# basicDueMega.net
KiCad netlist of a schematic drawn in EAGLE
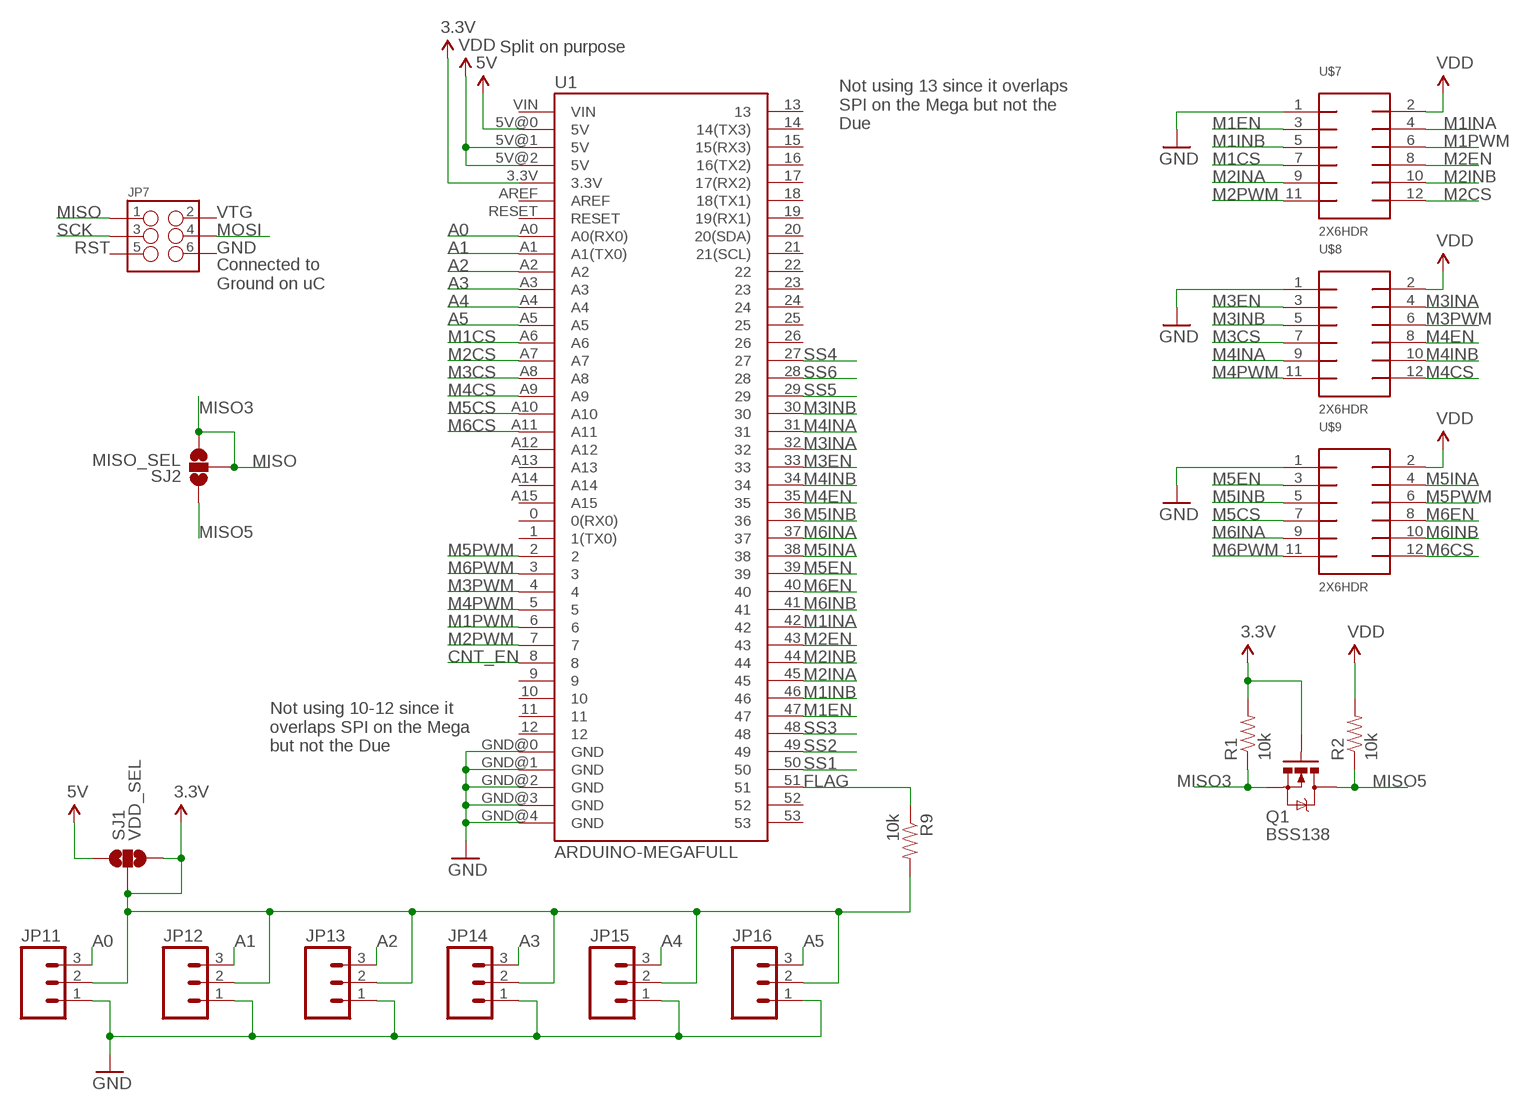
[diagram p0: schematic, sheet 1]
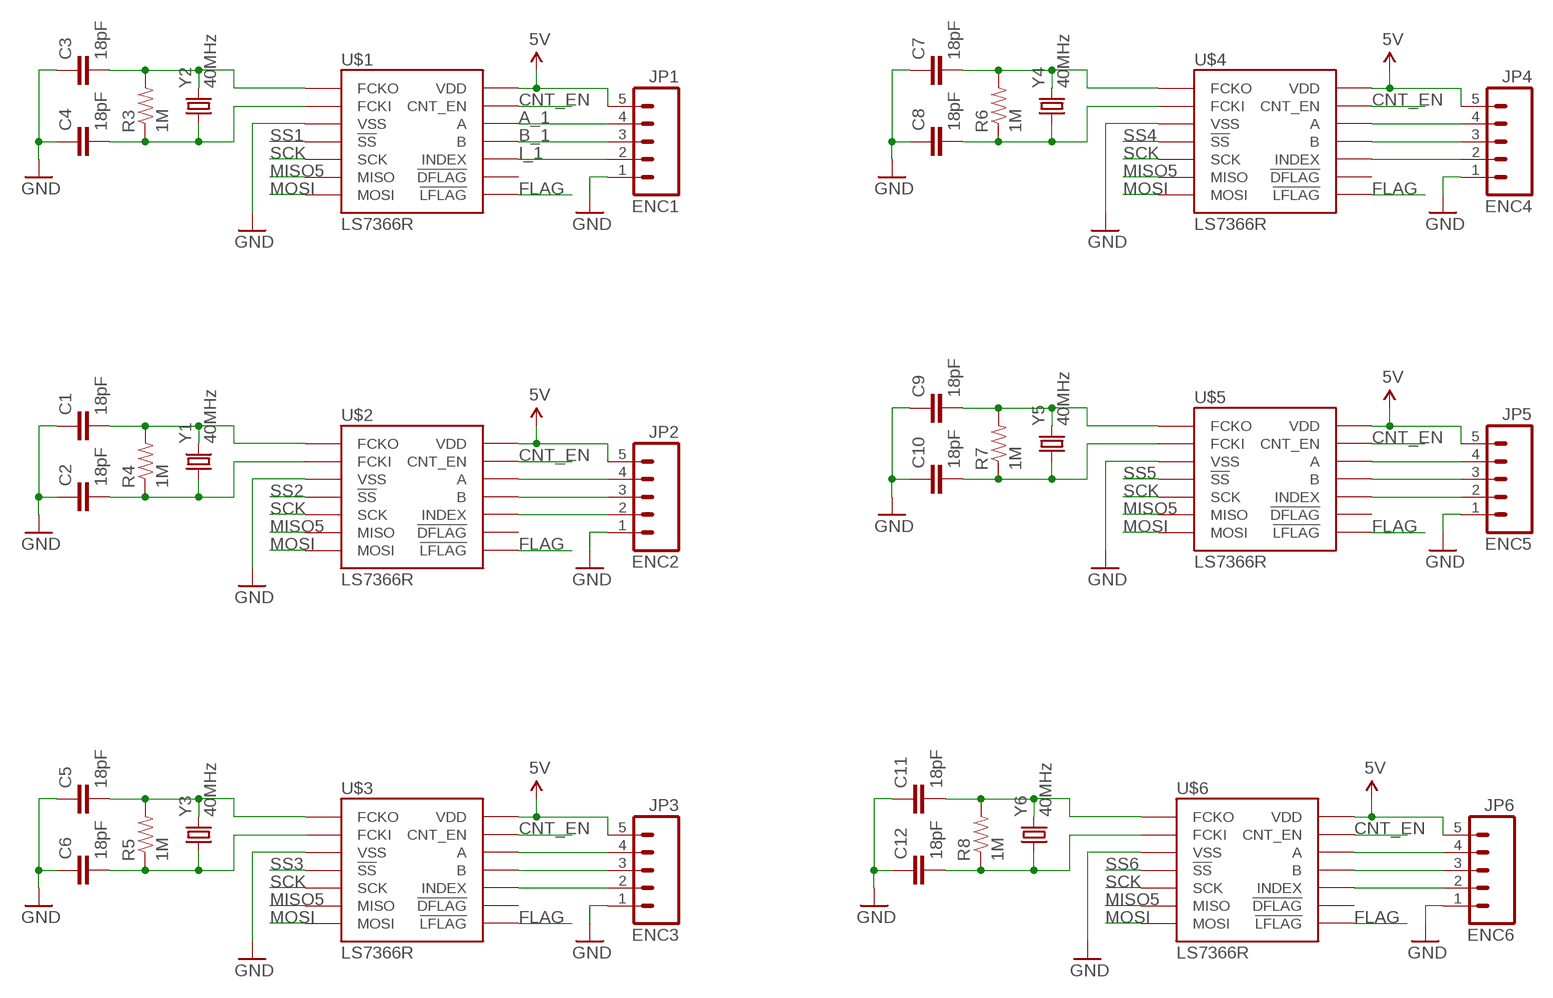
[diagram p1: schematic, sheet 2]

(export (version "E")
  (design (tool "Eeschema 10.0.6"))
  (components
    (comp (ref "C1")
      (value "18pF")
      (footprint "eagle-import:0603-CAP")
      (libsource (lib "eagle-import") (part "CAP0603-CAP"))
    )
    (comp (ref "C2")
      (value "18pF")
      (footprint "eagle-import:0603-CAP")
      (libsource (lib "eagle-import") (part "CAP0603-CAP"))
    )
    (comp (ref "C3")
      (value "18pF")
      (footprint "eagle-import:0603-CAP")
      (libsource (lib "eagle-import") (part "CAP0603-CAP"))
    )
    (comp (ref "C4")
      (value "18pF")
      (footprint "eagle-import:0603-CAP")
      (libsource (lib "eagle-import") (part "CAP0603-CAP"))
    )
    (comp (ref "C5")
      (value "18pF")
      (footprint "eagle-import:0603-CAP")
      (libsource (lib "eagle-import") (part "CAP0603-CAP"))
    )
    (comp (ref "C6")
      (value "18pF")
      (footprint "eagle-import:0603-CAP")
      (libsource (lib "eagle-import") (part "CAP0603-CAP"))
    )
    (comp (ref "C7")
      (value "18pF")
      (footprint "eagle-import:0603-CAP")
      (libsource (lib "eagle-import") (part "CAP0603-CAP"))
    )
    (comp (ref "C8")
      (value "18pF")
      (footprint "eagle-import:0603-CAP")
      (libsource (lib "eagle-import") (part "CAP0603-CAP"))
    )
    (comp (ref "C9")
      (value "18pF")
      (footprint "eagle-import:0603-CAP")
      (libsource (lib "eagle-import") (part "CAP0603-CAP"))
    )
    (comp (ref "C10")
      (value "18pF")
      (footprint "eagle-import:0603-CAP")
      (libsource (lib "eagle-import") (part "CAP0603-CAP"))
    )
    (comp (ref "C11")
      (value "18pF")
      (footprint "eagle-import:0603-CAP")
      (libsource (lib "eagle-import") (part "CAP0603-CAP"))
    )
    (comp (ref "C12")
      (value "18pF")
      (footprint "eagle-import:0603-CAP")
      (libsource (lib "eagle-import") (part "CAP0603-CAP"))
    )
    (comp (ref "JP1")
      (value "ENC1")
      (footprint "eagle-import:1X05_LOCK")
      (libsource (lib "eagle-import") (part "M05LOCK"))
    )
    (comp (ref "JP2")
      (value "ENC2")
      (footprint "eagle-import:1X05_LOCK")
      (libsource (lib "eagle-import") (part "M05LOCK"))
    )
    (comp (ref "JP3")
      (value "ENC3")
      (footprint "eagle-import:1X05_LOCK")
      (libsource (lib "eagle-import") (part "M05LOCK"))
    )
    (comp (ref "JP4")
      (value "ENC4")
      (footprint "eagle-import:1X05_LOCK")
      (libsource (lib "eagle-import") (part "M05LOCK"))
    )
    (comp (ref "JP5")
      (value "ENC5")
      (footprint "eagle-import:1X05_LOCK")
      (libsource (lib "eagle-import") (part "M05LOCK"))
    )
    (comp (ref "JP6")
      (value "ENC6")
      (footprint "eagle-import:1X05_LOCK")
      (libsource (lib "eagle-import") (part "M05LOCK"))
    )
    (comp (ref "R3")
      (value "1M")
      (footprint "eagle-import:0603-RES")
      (libsource (lib "eagle-import") (part "RESISTOR0603-RES"))
    )
    (comp (ref "R4")
      (value "1M")
      (footprint "eagle-import:0603-RES")
      (libsource (lib "eagle-import") (part "RESISTOR0603-RES"))
    )
    (comp (ref "R5")
      (value "1M")
      (footprint "eagle-import:0603-RES")
      (libsource (lib "eagle-import") (part "RESISTOR0603-RES"))
    )
    (comp (ref "R6")
      (value "1M")
      (footprint "eagle-import:0603-RES")
      (libsource (lib "eagle-import") (part "RESISTOR0603-RES"))
    )
    (comp (ref "R7")
      (value "1M")
      (footprint "eagle-import:0603-RES")
      (libsource (lib "eagle-import") (part "RESISTOR0603-RES"))
    )
    (comp (ref "R8")
      (value "1M")
      (footprint "eagle-import:0603-RES")
      (libsource (lib "eagle-import") (part "RESISTOR0603-RES"))
    )
    (comp (ref "U$1")
      (value "LS7366R")
      (footprint "eagle-import:SOIC14")
      (libsource (lib "eagle-import") (part "LS7366R"))
    )
    (comp (ref "U$2")
      (value "LS7366R")
      (footprint "eagle-import:SOIC14")
      (libsource (lib "eagle-import") (part "LS7366R"))
    )
    (comp (ref "U$3")
      (value "LS7366R")
      (footprint "eagle-import:SOIC14")
      (libsource (lib "eagle-import") (part "LS7366R"))
    )
    (comp (ref "U$4")
      (value "LS7366R")
      (footprint "eagle-import:SOIC14")
      (libsource (lib "eagle-import") (part "LS7366R"))
    )
    (comp (ref "U$5")
      (value "LS7366R")
      (footprint "eagle-import:SOIC14")
      (libsource (lib "eagle-import") (part "LS7366R"))
    )
    (comp (ref "U$6")
      (value "LS7366R")
      (footprint "eagle-import:SOIC14")
      (libsource (lib "eagle-import") (part "LS7366R"))
    )
    (comp (ref "Y1")
      (value "40MHz")
      (footprint "eagle-import:CRYSTAL-SMD-5X3")
      (libsource (lib "eagle-import") (part "CRYSTAL5X3"))
    )
    (comp (ref "Y2")
      (value "40MHz")
      (footprint "eagle-import:CRYSTAL-SMD-5X3")
      (libsource (lib "eagle-import") (part "CRYSTAL5X3"))
    )
    (comp (ref "Y3")
      (value "40MHz")
      (footprint "eagle-import:CRYSTAL-SMD-5X3")
      (libsource (lib "eagle-import") (part "CRYSTAL5X3"))
    )
    (comp (ref "Y4")
      (value "40MHz")
      (footprint "eagle-import:CRYSTAL-SMD-5X3")
      (libsource (lib "eagle-import") (part "CRYSTAL5X3"))
    )
    (comp (ref "Y5")
      (value "40MHz")
      (footprint "eagle-import:CRYSTAL-SMD-5X3")
      (libsource (lib "eagle-import") (part "CRYSTAL5X3"))
    )
    (comp (ref "Y6")
      (value "40MHz")
      (footprint "eagle-import:CRYSTAL-SMD-5X3")
      (libsource (lib "eagle-import") (part "CRYSTAL5X3"))
    )
    (comp (ref "JP7")
      (value "M03X2POGO_PINS")
      (footprint "eagle-import:2X3_POGO")
      (libsource (lib "eagle-import") (part "M03X2POGO_PINS"))
    )
    (comp (ref "JP11")
      (value "M03LOCK")
      (footprint "eagle-import:1X03_LOCK")
      (libsource (lib "eagle-import") (part "M03LOCK"))
    )
    (comp (ref "JP12")
      (value "M03LOCK")
      (footprint "eagle-import:1X03_LOCK")
      (libsource (lib "eagle-import") (part "M03LOCK"))
    )
    (comp (ref "JP13")
      (value "M03LOCK")
      (footprint "eagle-import:1X03_LOCK")
      (libsource (lib "eagle-import") (part "M03LOCK"))
    )
    (comp (ref "JP14")
      (value "M03LOCK")
      (footprint "eagle-import:1X03_LOCK")
      (libsource (lib "eagle-import") (part "M03LOCK"))
    )
    (comp (ref "JP15")
      (value "M03LOCK")
      (footprint "eagle-import:1X03_LOCK")
      (libsource (lib "eagle-import") (part "M03LOCK"))
    )
    (comp (ref "JP16")
      (value "M03LOCK")
      (footprint "eagle-import:1X03_LOCK")
      (libsource (lib "eagle-import") (part "M03LOCK"))
    )
    (comp (ref "Q1")
      (value "MOSFET-NCHANNELBSS123LT1G")
      (footprint "eagle-import:SOT23")
      (libsource (lib "eagle-import") (part "MOSFET-NCHANNELBSS123LT1G"))
    )
    (comp (ref "R1")
      (value "10k")
      (footprint "eagle-import:0603-RES")
      (libsource (lib "eagle-import") (part "RESISTOR0603-RES"))
    )
    (comp (ref "R2")
      (value "10k")
      (footprint "eagle-import:0603-RES")
      (libsource (lib "eagle-import") (part "RESISTOR0603-RES"))
    )
    (comp (ref "R9")
      (value "10k")
      (footprint "eagle-import:0603-RES")
      (libsource (lib "eagle-import") (part "RESISTOR0603-RES"))
    )
    (comp (ref "SJ1")
      (value "VDD_SEL")
      (footprint "eagle-import:SJ_2")
      (libsource (lib "eagle-import") (part "SOLDERJUMPER_2WAYT"))
    )
    (comp (ref "SJ2")
      (value "MISO_SEL")
      (footprint "eagle-import:SJ_2")
      (libsource (lib "eagle-import") (part "SOLDERJUMPER_2WAYT"))
    )
    (comp (ref "U$7")
      (value "2X6HDR")
      (footprint "eagle-import:2X6_2MM_SHROUD")
      (libsource (lib "eagle-import") (part "2X6HDR"))
    )
    (comp (ref "U$8")
      (value "2X6HDR")
      (footprint "eagle-import:2X6_2MM_SHROUD")
      (libsource (lib "eagle-import") (part "2X6HDR"))
    )
    (comp (ref "U$9")
      (value "2X6HDR")
      (footprint "eagle-import:2X6_2MM_SHROUD")
      (libsource (lib "eagle-import") (part "2X6HDR"))
    )
    (comp (ref "U1")
      (value "ARDUINO-MEGAFULL")
      (footprint "eagle-import:ARDUINO_MEGA")
      (libsource (lib "eagle-import") (part "ARDUINO-MEGAFULL"))
    )
  )
  (nets
    (net (code "1") (name "3.3V") (class "Default")
      (node (ref "JP11") (pin "2") (pinfunction "2_2") (pintype "passive"))
      (node (ref "JP12") (pin "2") (pinfunction "2_2") (pintype "passive"))
      (node (ref "JP13") (pin "2") (pinfunction "2_2") (pintype "passive"))
      (node (ref "JP14") (pin "2") (pinfunction "2_2") (pintype "passive"))
      (node (ref "JP15") (pin "2") (pinfunction "2_2") (pintype "passive"))
      (node (ref "JP16") (pin "2") (pinfunction "2_2") (pintype "passive"))
      (node (ref "Q1") (pin "1") (pinfunction "G_1") (pintype "passive"))
      (node (ref "R1") (pin "2") (pinfunction "2_2") (pintype "passive"))
      (node (ref "R9") (pin "2") (pinfunction "2_2") (pintype "passive"))
      (node (ref "SJ1") (pin "2") (pinfunction "2_2") (pintype "passive"))
      (node (ref "SJ1") (pin "3") (pinfunction "3_3") (pintype "passive"))
      (node (ref "U1") (pin "3.3V") (pinfunction "3.3V_3.3V") (pintype "bidirectional"))
    )
    (net (code "2") (name "5V") (class "Default")
      (node (ref "JP1") (pin "5") (pinfunction "5_5") (pintype "passive"))
      (node (ref "JP2") (pin "5") (pinfunction "5_5") (pintype "passive"))
      (node (ref "JP3") (pin "5") (pinfunction "5_5") (pintype "passive"))
      (node (ref "JP4") (pin "5") (pinfunction "5_5") (pintype "passive"))
      (node (ref "JP5") (pin "5") (pinfunction "5_5") (pintype "passive"))
      (node (ref "JP6") (pin "5") (pinfunction "5_5") (pintype "passive"))
      (node (ref "SJ1") (pin "1") (pinfunction "1_1") (pintype "passive"))
      (node (ref "U$1") (pin "14") (pinfunction "VDD_14") (pintype "bidirectional"))
      (node (ref "U$2") (pin "14") (pinfunction "VDD_14") (pintype "bidirectional"))
      (node (ref "U$3") (pin "14") (pinfunction "VDD_14") (pintype "bidirectional"))
      (node (ref "U$4") (pin "14") (pinfunction "VDD_14") (pintype "bidirectional"))
      (node (ref "U$5") (pin "14") (pinfunction "VDD_14") (pintype "bidirectional"))
      (node (ref "U$6") (pin "14") (pinfunction "VDD_14") (pintype "bidirectional"))
      (node (ref "U1") (pin "5V@0") (pinfunction "5V_5V@0") (pintype "bidirectional"))
    )
    (net (code "3") (name "A0") (class "Default")
      (node (ref "JP11") (pin "3") (pinfunction "3_3") (pintype "passive"))
      (node (ref "U1") (pin "A0") (pinfunction "A0(RX0)_A0") (pintype "bidirectional"))
    )
    (net (code "4") (name "A1") (class "Default")
      (node (ref "JP12") (pin "3") (pinfunction "3_3") (pintype "passive"))
      (node (ref "U1") (pin "A1") (pinfunction "A1(TX0)_A1") (pintype "bidirectional"))
    )
    (net (code "5") (name "A2") (class "Default")
      (node (ref "JP13") (pin "3") (pinfunction "3_3") (pintype "passive"))
      (node (ref "U1") (pin "A2") (pinfunction "A2_A2") (pintype "bidirectional"))
    )
    (net (code "6") (name "A3") (class "Default")
      (node (ref "JP14") (pin "3") (pinfunction "3_3") (pintype "passive"))
      (node (ref "U1") (pin "A3") (pinfunction "A3_A3") (pintype "bidirectional"))
    )
    (net (code "7") (name "A4") (class "Default")
      (node (ref "JP15") (pin "3") (pinfunction "3_3") (pintype "passive"))
      (node (ref "U1") (pin "A4") (pinfunction "A4_A4") (pintype "bidirectional"))
    )
    (net (code "8") (name "A5") (class "Default")
      (node (ref "JP16") (pin "3") (pinfunction "3_3") (pintype "passive"))
      (node (ref "U1") (pin "A5") (pinfunction "A5_A5") (pintype "bidirectional"))
    )
    (net (code "9") (name "A_1") (class "Default")
      (node (ref "JP1") (pin "4") (pinfunction "4_4") (pintype "passive"))
      (node (ref "U$1") (pin "12") (pinfunction "A_12") (pintype "bidirectional"))
    )
    (net (code "10") (name "B_1") (class "Default")
      (node (ref "JP1") (pin "3") (pinfunction "3_3") (pintype "passive"))
      (node (ref "U$1") (pin "11") (pinfunction "B_11") (pintype "bidirectional"))
    )
    (net (code "11") (name "CNT_EN") (class "Default")
      (node (ref "U$1") (pin "13") (pinfunction "CNT_EN_13") (pintype "bidirectional"))
      (node (ref "U$2") (pin "13") (pinfunction "CNT_EN_13") (pintype "bidirectional"))
      (node (ref "U$3") (pin "13") (pinfunction "CNT_EN_13") (pintype "bidirectional"))
      (node (ref "U$4") (pin "13") (pinfunction "CNT_EN_13") (pintype "bidirectional"))
      (node (ref "U$5") (pin "13") (pinfunction "CNT_EN_13") (pintype "bidirectional"))
      (node (ref "U$6") (pin "13") (pinfunction "CNT_EN_13") (pintype "bidirectional"))
      (node (ref "U1") (pin "8") (pinfunction "8_8") (pintype "bidirectional"))
    )
    (net (code "12") (name "FLAG") (class "Default")
      (node (ref "R9") (pin "1") (pinfunction "1_1") (pintype "passive"))
      (node (ref "U$1") (pin "8") (pinfunction "~{LFLAG}_8") (pintype "bidirectional"))
      (node (ref "U$2") (pin "8") (pinfunction "~{LFLAG}_8") (pintype "bidirectional"))
      (node (ref "U$3") (pin "8") (pinfunction "~{LFLAG}_8") (pintype "bidirectional"))
      (node (ref "U$4") (pin "8") (pinfunction "~{LFLAG}_8") (pintype "bidirectional"))
      (node (ref "U$5") (pin "8") (pinfunction "~{LFLAG}_8") (pintype "bidirectional"))
      (node (ref "U$6") (pin "8") (pinfunction "~{LFLAG}_8") (pintype "bidirectional"))
      (node (ref "U1") (pin "51") (pinfunction "51_51") (pintype "bidirectional"))
    )
    (net (code "13") (name "GND") (class "Default")
      (node (ref "C1") (pin "1") (pinfunction "1_1") (pintype "passive"))
      (node (ref "C10") (pin "1") (pinfunction "1_1") (pintype "passive"))
      (node (ref "C11") (pin "1") (pinfunction "1_1") (pintype "passive"))
      (node (ref "C12") (pin "1") (pinfunction "1_1") (pintype "passive"))
      (node (ref "C2") (pin "1") (pinfunction "1_1") (pintype "passive"))
      (node (ref "C3") (pin "1") (pinfunction "1_1") (pintype "passive"))
      (node (ref "C4") (pin "1") (pinfunction "1_1") (pintype "passive"))
      (node (ref "C5") (pin "1") (pinfunction "1_1") (pintype "passive"))
      (node (ref "C6") (pin "1") (pinfunction "1_1") (pintype "passive"))
      (node (ref "C7") (pin "1") (pinfunction "1_1") (pintype "passive"))
      (node (ref "C8") (pin "1") (pinfunction "1_1") (pintype "passive"))
      (node (ref "C9") (pin "1") (pinfunction "1_1") (pintype "passive"))
      (node (ref "JP1") (pin "1") (pinfunction "1_1") (pintype "passive"))
      (node (ref "JP11") (pin "1") (pinfunction "1_1") (pintype "passive"))
      (node (ref "JP12") (pin "1") (pinfunction "1_1") (pintype "passive"))
      (node (ref "JP13") (pin "1") (pinfunction "1_1") (pintype "passive"))
      (node (ref "JP14") (pin "1") (pinfunction "1_1") (pintype "passive"))
      (node (ref "JP15") (pin "1") (pinfunction "1_1") (pintype "passive"))
      (node (ref "JP16") (pin "1") (pinfunction "1_1") (pintype "passive"))
      (node (ref "JP2") (pin "1") (pinfunction "1_1") (pintype "passive"))
      (node (ref "JP3") (pin "1") (pinfunction "1_1") (pintype "passive"))
      (node (ref "JP4") (pin "1") (pinfunction "1_1") (pintype "passive"))
      (node (ref "JP5") (pin "1") (pinfunction "1_1") (pintype "passive"))
      (node (ref "JP6") (pin "1") (pinfunction "1_1") (pintype "passive"))
      (node (ref "U$1") (pin "3") (pinfunction "VSS_3") (pintype "bidirectional"))
      (node (ref "U$2") (pin "3") (pinfunction "VSS_3") (pintype "bidirectional"))
      (node (ref "U$3") (pin "3") (pinfunction "VSS_3") (pintype "bidirectional"))
      (node (ref "U$4") (pin "3") (pinfunction "VSS_3") (pintype "bidirectional"))
      (node (ref "U$5") (pin "3") (pinfunction "VSS_3") (pintype "bidirectional"))
      (node (ref "U$6") (pin "3") (pinfunction "VSS_3") (pintype "bidirectional"))
      (node (ref "U$7") (pin "1") (pinfunction "P$1_1") (pintype "bidirectional"))
      (node (ref "U$8") (pin "1") (pinfunction "P$1_1") (pintype "bidirectional"))
      (node (ref "U$9") (pin "1") (pinfunction "P$1_1") (pintype "bidirectional"))
      (node (ref "U1") (pin "GND@0") (pinfunction "GND_GND@0") (pintype "bidirectional"))
      (node (ref "U1") (pin "GND@1") (pinfunction "GND_GND@1") (pintype "bidirectional"))
      (node (ref "U1") (pin "GND@2") (pinfunction "GND_GND@2") (pintype "bidirectional"))
      (node (ref "U1") (pin "GND@3") (pinfunction "GND_GND@3") (pintype "bidirectional"))
      (node (ref "U1") (pin "GND@4") (pinfunction "GND_GND@4") (pintype "bidirectional"))
    )
    (net (code "14") (name "I_1") (class "Default")
      (node (ref "JP1") (pin "2") (pinfunction "2_2") (pintype "passive"))
      (node (ref "U$1") (pin "10") (pinfunction "INDEX_10") (pintype "bidirectional"))
    )
    (net (code "15") (name "M1CS") (class "Default")
      (node (ref "U$7") (pin "7") (pinfunction "P$7_7") (pintype "bidirectional"))
      (node (ref "U1") (pin "A6") (pinfunction "A6_A6") (pintype "bidirectional"))
    )
    (net (code "16") (name "M1EN") (class "Default")
      (node (ref "U$7") (pin "3") (pinfunction "P$3_3") (pintype "bidirectional"))
      (node (ref "U1") (pin "47") (pinfunction "47_47") (pintype "bidirectional"))
    )
    (net (code "17") (name "M1INA") (class "Default")
      (node (ref "U$7") (pin "4") (pinfunction "P$4_4") (pintype "bidirectional"))
      (node (ref "U1") (pin "42") (pinfunction "42_42") (pintype "bidirectional"))
    )
    (net (code "18") (name "M1INB") (class "Default")
      (node (ref "U$7") (pin "5") (pinfunction "P$5_5") (pintype "bidirectional"))
      (node (ref "U1") (pin "46") (pinfunction "46_46") (pintype "bidirectional"))
    )
    (net (code "19") (name "M1PWM") (class "Default")
      (node (ref "U$7") (pin "6") (pinfunction "P$6_6") (pintype "bidirectional"))
      (node (ref "U1") (pin "6") (pinfunction "6_6") (pintype "bidirectional"))
    )
    (net (code "20") (name "M2CS") (class "Default")
      (node (ref "U$7") (pin "12") (pinfunction "P$12_12") (pintype "bidirectional"))
      (node (ref "U1") (pin "A7") (pinfunction "A7_A7") (pintype "bidirectional"))
    )
    (net (code "21") (name "M2EN") (class "Default")
      (node (ref "U$7") (pin "8") (pinfunction "P$8_8") (pintype "bidirectional"))
      (node (ref "U1") (pin "43") (pinfunction "43_43") (pintype "bidirectional"))
    )
    (net (code "22") (name "M2INA") (class "Default")
      (node (ref "U$7") (pin "9") (pinfunction "P$9_9") (pintype "bidirectional"))
      (node (ref "U1") (pin "45") (pinfunction "45_45") (pintype "bidirectional"))
    )
    (net (code "23") (name "M2INB") (class "Default")
      (node (ref "U$7") (pin "10") (pinfunction "P$10_10") (pintype "bidirectional"))
      (node (ref "U1") (pin "44") (pinfunction "44_44") (pintype "bidirectional"))
    )
    (net (code "24") (name "M2PWM") (class "Default")
      (node (ref "U$7") (pin "11") (pinfunction "P$11_11") (pintype "bidirectional"))
      (node (ref "U1") (pin "7") (pinfunction "7_7") (pintype "bidirectional"))
    )
    (net (code "25") (name "M3CS") (class "Default")
      (node (ref "U$8") (pin "7") (pinfunction "P$7_7") (pintype "bidirectional"))
      (node (ref "U1") (pin "A8") (pinfunction "A8_A8") (pintype "bidirectional"))
    )
    (net (code "26") (name "M3EN") (class "Default")
      (node (ref "U$8") (pin "3") (pinfunction "P$3_3") (pintype "bidirectional"))
      (node (ref "U1") (pin "33") (pinfunction "33_33") (pintype "bidirectional"))
    )
    (net (code "27") (name "M3INA") (class "Default")
      (node (ref "U$8") (pin "4") (pinfunction "P$4_4") (pintype "bidirectional"))
      (node (ref "U1") (pin "32") (pinfunction "32_32") (pintype "bidirectional"))
    )
    (net (code "28") (name "M3INB") (class "Default")
      (node (ref "U$8") (pin "5") (pinfunction "P$5_5") (pintype "bidirectional"))
      (node (ref "U1") (pin "30") (pinfunction "30_30") (pintype "bidirectional"))
    )
    (net (code "29") (name "M3PWM") (class "Default")
      (node (ref "U$8") (pin "6") (pinfunction "P$6_6") (pintype "bidirectional"))
      (node (ref "U1") (pin "4") (pinfunction "4_4") (pintype "bidirectional"))
    )
    (net (code "30") (name "M4CS") (class "Default")
      (node (ref "U$8") (pin "12") (pinfunction "P$12_12") (pintype "bidirectional"))
      (node (ref "U1") (pin "A9") (pinfunction "A9_A9") (pintype "bidirectional"))
    )
    (net (code "31") (name "M4EN") (class "Default")
      (node (ref "U$8") (pin "8") (pinfunction "P$8_8") (pintype "bidirectional"))
      (node (ref "U1") (pin "35") (pinfunction "35_35") (pintype "bidirectional"))
    )
    (net (code "32") (name "M4INA") (class "Default")
      (node (ref "U$8") (pin "9") (pinfunction "P$9_9") (pintype "bidirectional"))
      (node (ref "U1") (pin "31") (pinfunction "31_31") (pintype "bidirectional"))
    )
    (net (code "33") (name "M4INB") (class "Default")
      (node (ref "U$8") (pin "10") (pinfunction "P$10_10") (pintype "bidirectional"))
      (node (ref "U1") (pin "34") (pinfunction "34_34") (pintype "bidirectional"))
    )
    (net (code "34") (name "M4PWM") (class "Default")
      (node (ref "U$8") (pin "11") (pinfunction "P$11_11") (pintype "bidirectional"))
      (node (ref "U1") (pin "5") (pinfunction "5_5") (pintype "bidirectional"))
    )
    (net (code "35") (name "M5CS") (class "Default")
      (node (ref "U$9") (pin "7") (pinfunction "P$7_7") (pintype "bidirectional"))
      (node (ref "U1") (pin "A10") (pinfunction "A10_A10") (pintype "bidirectional"))
    )
    (net (code "36") (name "M5EN") (class "Default")
      (node (ref "U$9") (pin "3") (pinfunction "P$3_3") (pintype "bidirectional"))
      (node (ref "U1") (pin "39") (pinfunction "39_39") (pintype "bidirectional"))
    )
    (net (code "37") (name "M5INA") (class "Default")
      (node (ref "U$9") (pin "4") (pinfunction "P$4_4") (pintype "bidirectional"))
      (node (ref "U1") (pin "38") (pinfunction "38_38") (pintype "bidirectional"))
    )
    (net (code "38") (name "M5INB") (class "Default")
      (node (ref "U$9") (pin "5") (pinfunction "P$5_5") (pintype "bidirectional"))
      (node (ref "U1") (pin "36") (pinfunction "36_36") (pintype "bidirectional"))
    )
    (net (code "39") (name "M5PWM") (class "Default")
      (node (ref "U$9") (pin "6") (pinfunction "P$6_6") (pintype "bidirectional"))
      (node (ref "U1") (pin "2") (pinfunction "2_2") (pintype "bidirectional"))
    )
    (net (code "40") (name "M6CS") (class "Default")
      (node (ref "U$9") (pin "12") (pinfunction "P$12_12") (pintype "bidirectional"))
      (node (ref "U1") (pin "A11") (pinfunction "A11_A11") (pintype "bidirectional"))
    )
    (net (code "41") (name "M6EN") (class "Default")
      (node (ref "U$9") (pin "8") (pinfunction "P$8_8") (pintype "bidirectional"))
      (node (ref "U1") (pin "40") (pinfunction "40_40") (pintype "bidirectional"))
    )
    (net (code "42") (name "M6INA") (class "Default")
      (node (ref "U$9") (pin "9") (pinfunction "P$9_9") (pintype "bidirectional"))
      (node (ref "U1") (pin "37") (pinfunction "37_37") (pintype "bidirectional"))
    )
    (net (code "43") (name "M6INB") (class "Default")
      (node (ref "U$9") (pin "10") (pinfunction "P$10_10") (pintype "bidirectional"))
      (node (ref "U1") (pin "41") (pinfunction "41_41") (pintype "bidirectional"))
    )
    (net (code "44") (name "M6PWM") (class "Default")
      (node (ref "U$9") (pin "11") (pinfunction "P$11_11") (pintype "bidirectional"))
      (node (ref "U1") (pin "3") (pinfunction "3_3") (pintype "bidirectional"))
    )
    (net (code "45") (name "MISO3") (class "Default")
      (node (ref "JP7") (pin "P$1") (pinfunction "1_P$1") (pintype "bidirectional"))
      (node (ref "Q1") (pin "2") (pinfunction "S_2") (pintype "passive"))
      (node (ref "R1") (pin "1") (pinfunction "1_1") (pintype "passive"))
      (node (ref "SJ2") (pin "2") (pinfunction "2_2") (pintype "passive"))
      (node (ref "SJ2") (pin "3") (pinfunction "3_3") (pintype "passive"))
    )
    (net (code "46") (name "MISO5") (class "Default")
      (node (ref "Q1") (pin "3") (pinfunction "D_3") (pintype "passive"))
      (node (ref "R2") (pin "1") (pinfunction "1_1") (pintype "passive"))
      (node (ref "SJ2") (pin "1") (pinfunction "1_1") (pintype "passive"))
      (node (ref "U$1") (pin "6") (pinfunction "MISO_6") (pintype "bidirectional"))
      (node (ref "U$2") (pin "6") (pinfunction "MISO_6") (pintype "bidirectional"))
      (node (ref "U$3") (pin "6") (pinfunction "MISO_6") (pintype "bidirectional"))
      (node (ref "U$4") (pin "6") (pinfunction "MISO_6") (pintype "bidirectional"))
      (node (ref "U$5") (pin "6") (pinfunction "MISO_6") (pintype "bidirectional"))
      (node (ref "U$6") (pin "6") (pinfunction "MISO_6") (pintype "bidirectional"))
    )
    (net (code "47") (name "MOSI") (class "Default")
      (node (ref "JP7") (pin "P$4") (pinfunction "4_P$4") (pintype "bidirectional"))
      (node (ref "U$1") (pin "7") (pinfunction "MOSI_7") (pintype "bidirectional"))
      (node (ref "U$2") (pin "7") (pinfunction "MOSI_7") (pintype "bidirectional"))
      (node (ref "U$3") (pin "7") (pinfunction "MOSI_7") (pintype "bidirectional"))
      (node (ref "U$4") (pin "7") (pinfunction "MOSI_7") (pintype "bidirectional"))
      (node (ref "U$5") (pin "7") (pinfunction "MOSI_7") (pintype "bidirectional"))
      (node (ref "U$6") (pin "7") (pinfunction "MOSI_7") (pintype "bidirectional"))
    )
    (net (code "48") (name "Net-(U$1-FCKI)") (class "Default")
      (node (ref "C4") (pin "2") (pinfunction "2_2") (pintype "passive"))
      (node (ref "R3") (pin "1") (pinfunction "1_1") (pintype "passive"))
      (node (ref "U$1") (pin "2") (pinfunction "FCKI_2") (pintype "bidirectional"))
      (node (ref "Y2") (pin "1") (pinfunction "1_1") (pintype "passive"))
    )
    (net (code "49") (name "Net-(U$1-FCKO)") (class "Default")
      (node (ref "C3") (pin "2") (pinfunction "2_2") (pintype "passive"))
      (node (ref "R3") (pin "2") (pinfunction "2_2") (pintype "passive"))
      (node (ref "U$1") (pin "1") (pinfunction "FCKO_1") (pintype "bidirectional"))
      (node (ref "Y2") (pin "3") (pinfunction "2_3") (pintype "passive"))
    )
    (net (code "50") (name "Net-(U$2-A)") (class "Default")
      (node (ref "JP2") (pin "4") (pinfunction "4_4") (pintype "passive"))
      (node (ref "U$2") (pin "12") (pinfunction "A_12") (pintype "bidirectional"))
    )
    (net (code "51") (name "Net-(U$2-B)") (class "Default")
      (node (ref "JP2") (pin "3") (pinfunction "3_3") (pintype "passive"))
      (node (ref "U$2") (pin "11") (pinfunction "B_11") (pintype "bidirectional"))
    )
    (net (code "52") (name "Net-(U$2-FCKI)") (class "Default")
      (node (ref "C2") (pin "2") (pinfunction "2_2") (pintype "passive"))
      (node (ref "R4") (pin "1") (pinfunction "1_1") (pintype "passive"))
      (node (ref "U$2") (pin "2") (pinfunction "FCKI_2") (pintype "bidirectional"))
      (node (ref "Y1") (pin "1") (pinfunction "1_1") (pintype "passive"))
    )
    (net (code "53") (name "Net-(U$2-FCKO)") (class "Default")
      (node (ref "C1") (pin "2") (pinfunction "2_2") (pintype "passive"))
      (node (ref "R4") (pin "2") (pinfunction "2_2") (pintype "passive"))
      (node (ref "U$2") (pin "1") (pinfunction "FCKO_1") (pintype "bidirectional"))
      (node (ref "Y1") (pin "3") (pinfunction "2_3") (pintype "passive"))
    )
    (net (code "54") (name "Net-(U$2-INDEX)") (class "Default")
      (node (ref "JP2") (pin "2") (pinfunction "2_2") (pintype "passive"))
      (node (ref "U$2") (pin "10") (pinfunction "INDEX_10") (pintype "bidirectional"))
    )
    (net (code "55") (name "Net-(U$3-A)") (class "Default")
      (node (ref "JP3") (pin "4") (pinfunction "4_4") (pintype "passive"))
      (node (ref "U$3") (pin "12") (pinfunction "A_12") (pintype "bidirectional"))
    )
    (net (code "56") (name "Net-(U$3-B)") (class "Default")
      (node (ref "JP3") (pin "3") (pinfunction "3_3") (pintype "passive"))
      (node (ref "U$3") (pin "11") (pinfunction "B_11") (pintype "bidirectional"))
    )
    (net (code "57") (name "Net-(U$3-FCKI)") (class "Default")
      (node (ref "C6") (pin "2") (pinfunction "2_2") (pintype "passive"))
      (node (ref "R5") (pin "1") (pinfunction "1_1") (pintype "passive"))
      (node (ref "U$3") (pin "2") (pinfunction "FCKI_2") (pintype "bidirectional"))
      (node (ref "Y3") (pin "1") (pinfunction "1_1") (pintype "passive"))
    )
    (net (code "58") (name "Net-(U$3-FCKO)") (class "Default")
      (node (ref "C5") (pin "2") (pinfunction "2_2") (pintype "passive"))
      (node (ref "R5") (pin "2") (pinfunction "2_2") (pintype "passive"))
      (node (ref "U$3") (pin "1") (pinfunction "FCKO_1") (pintype "bidirectional"))
      (node (ref "Y3") (pin "3") (pinfunction "2_3") (pintype "passive"))
    )
    (net (code "59") (name "Net-(U$3-INDEX)") (class "Default")
      (node (ref "JP3") (pin "2") (pinfunction "2_2") (pintype "passive"))
      (node (ref "U$3") (pin "10") (pinfunction "INDEX_10") (pintype "bidirectional"))
    )
    (net (code "60") (name "Net-(U$4-A)") (class "Default")
      (node (ref "JP4") (pin "4") (pinfunction "4_4") (pintype "passive"))
      (node (ref "U$4") (pin "12") (pinfunction "A_12") (pintype "bidirectional"))
    )
    (net (code "61") (name "Net-(U$4-B)") (class "Default")
      (node (ref "JP4") (pin "3") (pinfunction "3_3") (pintype "passive"))
      (node (ref "U$4") (pin "11") (pinfunction "B_11") (pintype "bidirectional"))
    )
    (net (code "62") (name "Net-(U$4-FCKI)") (class "Default")
      (node (ref "C8") (pin "2") (pinfunction "2_2") (pintype "passive"))
      (node (ref "R6") (pin "1") (pinfunction "1_1") (pintype "passive"))
      (node (ref "U$4") (pin "2") (pinfunction "FCKI_2") (pintype "bidirectional"))
      (node (ref "Y4") (pin "1") (pinfunction "1_1") (pintype "passive"))
    )
    (net (code "63") (name "Net-(U$4-FCKO)") (class "Default")
      (node (ref "C7") (pin "2") (pinfunction "2_2") (pintype "passive"))
      (node (ref "R6") (pin "2") (pinfunction "2_2") (pintype "passive"))
      (node (ref "U$4") (pin "1") (pinfunction "FCKO_1") (pintype "bidirectional"))
      (node (ref "Y4") (pin "3") (pinfunction "2_3") (pintype "passive"))
    )
    (net (code "64") (name "Net-(U$4-INDEX)") (class "Default")
      (node (ref "JP4") (pin "2") (pinfunction "2_2") (pintype "passive"))
      (node (ref "U$4") (pin "10") (pinfunction "INDEX_10") (pintype "bidirectional"))
    )
    (net (code "65") (name "Net-(U$5-A)") (class "Default")
      (node (ref "JP5") (pin "4") (pinfunction "4_4") (pintype "passive"))
      (node (ref "U$5") (pin "12") (pinfunction "A_12") (pintype "bidirectional"))
    )
    (net (code "66") (name "Net-(U$5-B)") (class "Default")
      (node (ref "JP5") (pin "3") (pinfunction "3_3") (pintype "passive"))
      (node (ref "U$5") (pin "11") (pinfunction "B_11") (pintype "bidirectional"))
    )
    (net (code "67") (name "Net-(U$5-FCKI)") (class "Default")
      (node (ref "C10") (pin "2") (pinfunction "2_2") (pintype "passive"))
      (node (ref "R7") (pin "1") (pinfunction "1_1") (pintype "passive"))
      (node (ref "U$5") (pin "2") (pinfunction "FCKI_2") (pintype "bidirectional"))
      (node (ref "Y5") (pin "1") (pinfunction "1_1") (pintype "passive"))
    )
    (net (code "68") (name "Net-(U$5-FCKO)") (class "Default")
      (node (ref "C9") (pin "2") (pinfunction "2_2") (pintype "passive"))
      (node (ref "R7") (pin "2") (pinfunction "2_2") (pintype "passive"))
      (node (ref "U$5") (pin "1") (pinfunction "FCKO_1") (pintype "bidirectional"))
      (node (ref "Y5") (pin "3") (pinfunction "2_3") (pintype "passive"))
    )
    (net (code "69") (name "Net-(U$5-INDEX)") (class "Default")
      (node (ref "JP5") (pin "2") (pinfunction "2_2") (pintype "passive"))
      (node (ref "U$5") (pin "10") (pinfunction "INDEX_10") (pintype "bidirectional"))
    )
    (net (code "70") (name "Net-(U$6-A)") (class "Default")
      (node (ref "JP6") (pin "4") (pinfunction "4_4") (pintype "passive"))
      (node (ref "U$6") (pin "12") (pinfunction "A_12") (pintype "bidirectional"))
    )
    (net (code "71") (name "Net-(U$6-B)") (class "Default")
      (node (ref "JP6") (pin "3") (pinfunction "3_3") (pintype "passive"))
      (node (ref "U$6") (pin "11") (pinfunction "B_11") (pintype "bidirectional"))
    )
    (net (code "72") (name "Net-(U$6-FCKI)") (class "Default")
      (node (ref "C12") (pin "2") (pinfunction "2_2") (pintype "passive"))
      (node (ref "R8") (pin "1") (pinfunction "1_1") (pintype "passive"))
      (node (ref "U$6") (pin "2") (pinfunction "FCKI_2") (pintype "bidirectional"))
      (node (ref "Y6") (pin "1") (pinfunction "1_1") (pintype "passive"))
    )
    (net (code "73") (name "Net-(U$6-FCKO)") (class "Default")
      (node (ref "C11") (pin "2") (pinfunction "2_2") (pintype "passive"))
      (node (ref "R8") (pin "2") (pinfunction "2_2") (pintype "passive"))
      (node (ref "U$6") (pin "1") (pinfunction "FCKO_1") (pintype "bidirectional"))
      (node (ref "Y6") (pin "3") (pinfunction "2_3") (pintype "passive"))
    )
    (net (code "74") (name "Net-(U$6-INDEX)") (class "Default")
      (node (ref "JP6") (pin "2") (pinfunction "2_2") (pintype "passive"))
      (node (ref "U$6") (pin "10") (pinfunction "INDEX_10") (pintype "bidirectional"))
    )
    (net (code "75") (name "SCK") (class "Default")
      (node (ref "JP7") (pin "P$3") (pinfunction "3_P$3") (pintype "bidirectional"))
      (node (ref "U$1") (pin "5") (pinfunction "SCK_5") (pintype "bidirectional"))
      (node (ref "U$2") (pin "5") (pinfunction "SCK_5") (pintype "bidirectional"))
      (node (ref "U$3") (pin "5") (pinfunction "SCK_5") (pintype "bidirectional"))
      (node (ref "U$4") (pin "5") (pinfunction "SCK_5") (pintype "bidirectional"))
      (node (ref "U$5") (pin "5") (pinfunction "SCK_5") (pintype "bidirectional"))
      (node (ref "U$6") (pin "5") (pinfunction "SCK_5") (pintype "bidirectional"))
    )
    (net (code "76") (name "SS1") (class "Default")
      (node (ref "U$1") (pin "4") (pinfunction "~{SS}_4") (pintype "bidirectional"))
      (node (ref "U1") (pin "50") (pinfunction "50_50") (pintype "bidirectional"))
    )
    (net (code "77") (name "SS2") (class "Default")
      (node (ref "U$2") (pin "4") (pinfunction "~{SS}_4") (pintype "bidirectional"))
      (node (ref "U1") (pin "49") (pinfunction "49_49") (pintype "bidirectional"))
    )
    (net (code "78") (name "SS3") (class "Default")
      (node (ref "U$3") (pin "4") (pinfunction "~{SS}_4") (pintype "bidirectional"))
      (node (ref "U1") (pin "48") (pinfunction "48_48") (pintype "bidirectional"))
    )
    (net (code "79") (name "SS4") (class "Default")
      (node (ref "U$4") (pin "4") (pinfunction "~{SS}_4") (pintype "bidirectional"))
      (node (ref "U1") (pin "27") (pinfunction "27_27") (pintype "bidirectional"))
    )
    (net (code "80") (name "SS5") (class "Default")
      (node (ref "U$5") (pin "4") (pinfunction "~{SS}_4") (pintype "bidirectional"))
      (node (ref "U1") (pin "29") (pinfunction "29_29") (pintype "bidirectional"))
    )
    (net (code "81") (name "SS6") (class "Default")
      (node (ref "U$6") (pin "4") (pinfunction "~{SS}_4") (pintype "bidirectional"))
      (node (ref "U1") (pin "28") (pinfunction "28_28") (pintype "bidirectional"))
    )
    (net (code "82") (name "VDD") (class "Default")
      (node (ref "R2") (pin "2") (pinfunction "2_2") (pintype "passive"))
      (node (ref "U$7") (pin "2") (pinfunction "P$2_2") (pintype "bidirectional"))
      (node (ref "U$8") (pin "2") (pinfunction "P$2_2") (pintype "bidirectional"))
      (node (ref "U$9") (pin "2") (pinfunction "P$2_2") (pintype "bidirectional"))
      (node (ref "U1") (pin "5V@1") (pinfunction "5V_5V@1") (pintype "bidirectional"))
      (node (ref "U1") (pin "5V@2") (pinfunction "5V_5V@2") (pintype "bidirectional"))
    )
    (net (code "83") (name "unconnected-(JP7-2-PadP$2)") (class "Default")
      (node (ref "JP7") (pin "P$2") (pinfunction "2_P$2") (pintype "bidirectional"))
    )
    (net (code "84") (name "unconnected-(JP7-5-PadP$5)") (class "Default")
      (node (ref "JP7") (pin "P$5") (pinfunction "5_P$5") (pintype "bidirectional"))
    )
    (net (code "85") (name "unconnected-(JP7-6-PadP$6)") (class "Default")
      (node (ref "JP7") (pin "P$6") (pinfunction "6_P$6") (pintype "bidirectional"))
    )
    (net (code "86") (name "unconnected-(U$1-~{DFLAG}-Pad9)") (class "Default")
      (node (ref "U$1") (pin "9") (pinfunction "~{DFLAG}_9") (pintype "bidirectional"))
    )
    (net (code "87") (name "unconnected-(U$2-~{DFLAG}-Pad9)") (class "Default")
      (node (ref "U$2") (pin "9") (pinfunction "~{DFLAG}_9") (pintype "bidirectional"))
    )
    (net (code "88") (name "unconnected-(U$3-~{DFLAG}-Pad9)") (class "Default")
      (node (ref "U$3") (pin "9") (pinfunction "~{DFLAG}_9") (pintype "bidirectional"))
    )
    (net (code "89") (name "unconnected-(U$4-~{DFLAG}-Pad9)") (class "Default")
      (node (ref "U$4") (pin "9") (pinfunction "~{DFLAG}_9") (pintype "bidirectional"))
    )
    (net (code "90") (name "unconnected-(U$5-~{DFLAG}-Pad9)") (class "Default")
      (node (ref "U$5") (pin "9") (pinfunction "~{DFLAG}_9") (pintype "bidirectional"))
    )
    (net (code "91") (name "unconnected-(U$6-~{DFLAG}-Pad9)") (class "Default")
      (node (ref "U$6") (pin "9") (pinfunction "~{DFLAG}_9") (pintype "bidirectional"))
    )
    (net (code "92") (name "unconnected-(U1-0(RX0)-Pad0)") (class "Default")
      (node (ref "U1") (pin "0") (pinfunction "0(RX0)_0") (pintype "bidirectional"))
    )
    (net (code "93") (name "unconnected-(U1-1(TX0)-Pad1)") (class "Default")
      (node (ref "U1") (pin "1") (pinfunction "1(TX0)_1") (pintype "bidirectional"))
    )
    (net (code "94") (name "unconnected-(U1-14(TX3)-Pad14)") (class "Default")
      (node (ref "U1") (pin "14") (pinfunction "14(TX3)_14") (pintype "bidirectional"))
    )
    (net (code "95") (name "unconnected-(U1-15(RX3)-Pad15)") (class "Default")
      (node (ref "U1") (pin "15") (pinfunction "15(RX3)_15") (pintype "bidirectional"))
    )
    (net (code "96") (name "unconnected-(U1-16(TX2)-Pad16)") (class "Default")
      (node (ref "U1") (pin "16") (pinfunction "16(TX2)_16") (pintype "bidirectional"))
    )
    (net (code "97") (name "unconnected-(U1-17(RX2)-Pad17)") (class "Default")
      (node (ref "U1") (pin "17") (pinfunction "17(RX2)_17") (pintype "bidirectional"))
    )
    (net (code "98") (name "unconnected-(U1-18(TX1)-Pad18)") (class "Default")
      (node (ref "U1") (pin "18") (pinfunction "18(TX1)_18") (pintype "bidirectional"))
    )
    (net (code "99") (name "unconnected-(U1-19(RX1)-Pad19)") (class "Default")
      (node (ref "U1") (pin "19") (pinfunction "19(RX1)_19") (pintype "bidirectional"))
    )
    (net (code "100") (name "unconnected-(U1-20(SDA)-Pad20)") (class "Default")
      (node (ref "U1") (pin "20") (pinfunction "20(SDA)_20") (pintype "bidirectional"))
    )
    (net (code "101") (name "unconnected-(U1-21(SCL)-Pad21)") (class "Default")
      (node (ref "U1") (pin "21") (pinfunction "21(SCL)_21") (pintype "bidirectional"))
    )
    (net (code "102") (name "unconnected-(U1-Pad9)") (class "Default")
      (node (ref "U1") (pin "9") (pinfunction "9_9") (pintype "bidirectional"))
    )
    (net (code "103") (name "unconnected-(U1-Pad10)") (class "Default")
      (node (ref "U1") (pin "10") (pinfunction "10_10") (pintype "bidirectional"))
    )
    (net (code "104") (name "unconnected-(U1-Pad11)") (class "Default")
      (node (ref "U1") (pin "11") (pinfunction "11_11") (pintype "bidirectional"))
    )
    (net (code "105") (name "unconnected-(U1-Pad12)") (class "Default")
      (node (ref "U1") (pin "12") (pinfunction "12_12") (pintype "bidirectional"))
    )
    (net (code "106") (name "unconnected-(U1-Pad13)") (class "Default")
      (node (ref "U1") (pin "13") (pinfunction "13_13") (pintype "bidirectional"))
    )
    (net (code "107") (name "unconnected-(U1-Pad22)") (class "Default")
      (node (ref "U1") (pin "22") (pinfunction "22_22") (pintype "bidirectional"))
    )
    (net (code "108") (name "unconnected-(U1-Pad23)") (class "Default")
      (node (ref "U1") (pin "23") (pinfunction "23_23") (pintype "bidirectional"))
    )
    (net (code "109") (name "unconnected-(U1-Pad24)") (class "Default")
      (node (ref "U1") (pin "24") (pinfunction "24_24") (pintype "bidirectional"))
    )
    (net (code "110") (name "unconnected-(U1-Pad25)") (class "Default")
      (node (ref "U1") (pin "25") (pinfunction "25_25") (pintype "bidirectional"))
    )
    (net (code "111") (name "unconnected-(U1-Pad26)") (class "Default")
      (node (ref "U1") (pin "26") (pinfunction "26_26") (pintype "bidirectional"))
    )
    (net (code "112") (name "unconnected-(U1-Pad52)") (class "Default")
      (node (ref "U1") (pin "52") (pinfunction "52_52") (pintype "bidirectional"))
    )
    (net (code "113") (name "unconnected-(U1-Pad53)") (class "Default")
      (node (ref "U1") (pin "53") (pinfunction "53_53") (pintype "bidirectional"))
    )
    (net (code "114") (name "unconnected-(U1-PadA12)") (class "Default")
      (node (ref "U1") (pin "A12") (pinfunction "A12_A12") (pintype "bidirectional"))
    )
    (net (code "115") (name "unconnected-(U1-PadA13)") (class "Default")
      (node (ref "U1") (pin "A13") (pinfunction "A13_A13") (pintype "bidirectional"))
    )
    (net (code "116") (name "unconnected-(U1-PadA14)") (class "Default")
      (node (ref "U1") (pin "A14") (pinfunction "A14_A14") (pintype "bidirectional"))
    )
    (net (code "117") (name "unconnected-(U1-PadA15)") (class "Default")
      (node (ref "U1") (pin "A15") (pinfunction "A15_A15") (pintype "bidirectional"))
    )
    (net (code "118") (name "unconnected-(U1-PadAREF)") (class "Default")
      (node (ref "U1") (pin "AREF") (pinfunction "AREF_AREF") (pintype "bidirectional"))
    )
    (net (code "119") (name "unconnected-(U1-PadRESET)") (class "Default")
      (node (ref "U1") (pin "RESET") (pinfunction "RESET_RESET") (pintype "bidirectional"))
    )
    (net (code "120") (name "unconnected-(U1-PadVIN)") (class "Default")
      (node (ref "U1") (pin "VIN") (pinfunction "VIN_VIN") (pintype "bidirectional"))
    )
  )
)
